# plugV6-Relay-NC-1.net
KiCad netlist of a schematic drawn in EAGLE
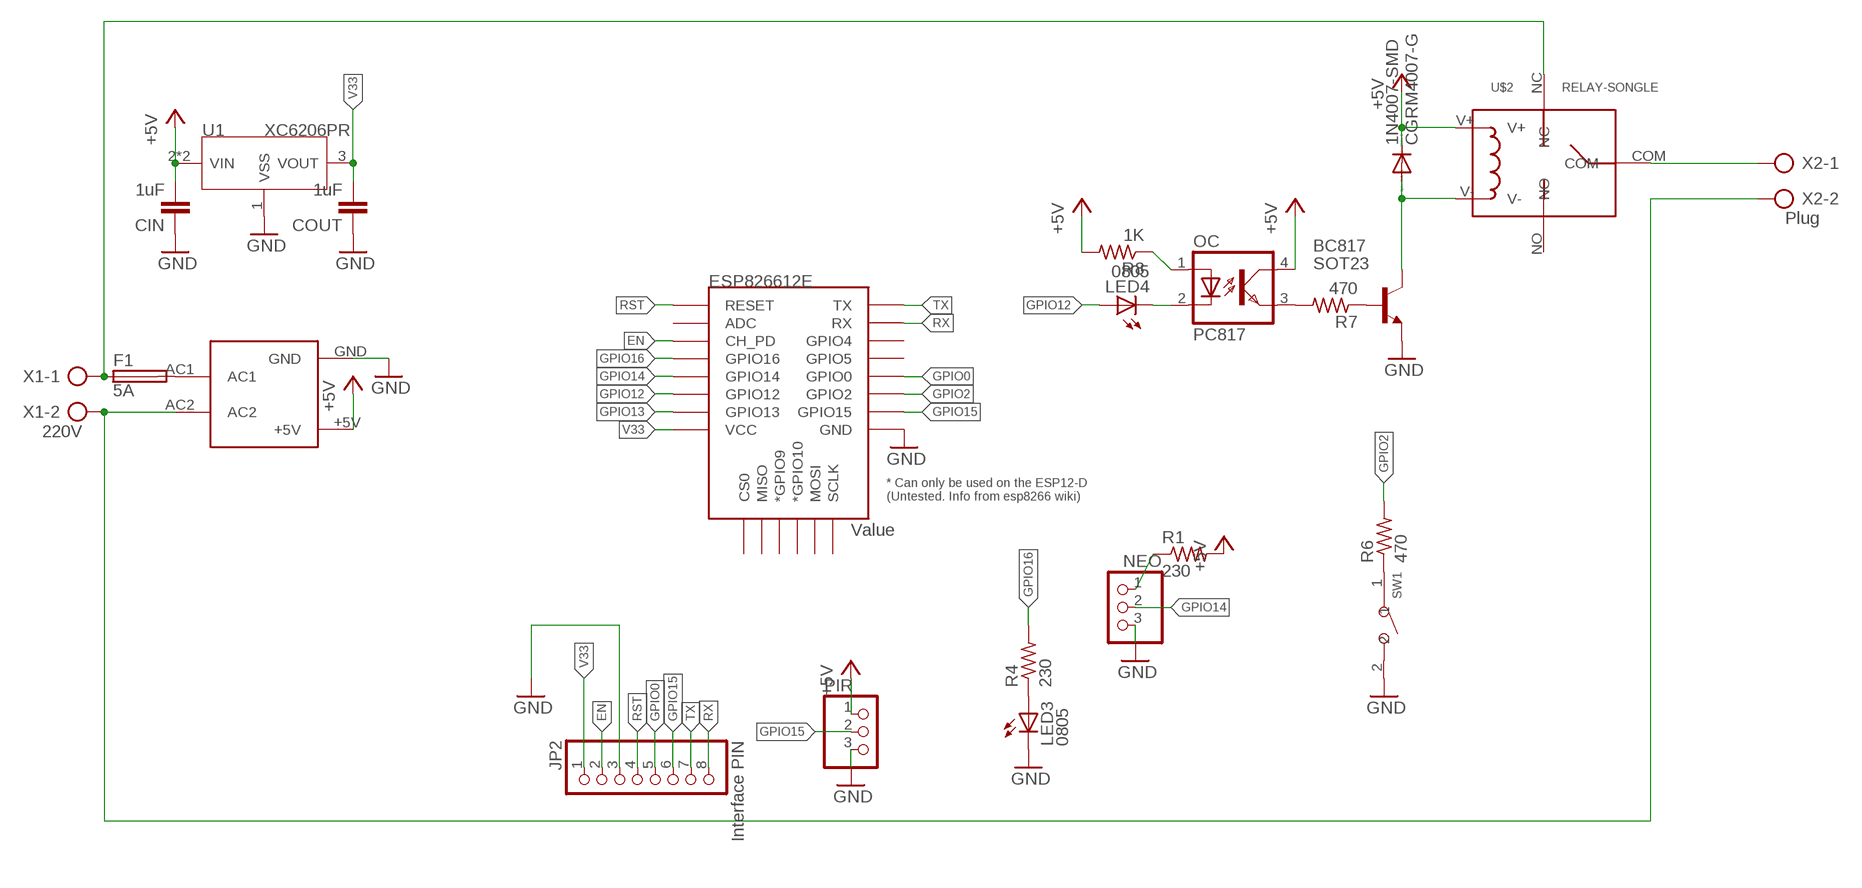
[diagram p0: schematic, sheet 1]

(export (version "E")
  (design (tool "Eeschema 10.0.6"))
  (components
    (comp (ref "1N4007-SMD")
      (value "CGRM4007-G")
      (footprint "eagle-import:SOD-123_MINI-SMA")
      (libsource (lib "eagle-import") (part "CGRM400-G7"))
    )
    (comp (ref "BC817")
      (value "SOT23")
      (footprint "eagle-import:SOT23-BEC")
      (libsource (lib "eagle-import") (part "-NPN-SOT23-BECBC817"))
    )
    (comp (ref "CIN")
      (value "1uF")
      (footprint "eagle-import:C0805")
      (libsource (lib "eagle-import") (part "C-EUC0805"))
    )
    (comp (ref "COUT")
      (value "1uF")
      (footprint "eagle-import:C0805")
      (libsource (lib "eagle-import") (part "C-EUC0805"))
    )
    (comp (ref "ESP826612E")
      (value "Value")
      (footprint "eagle-import:ESP12E-SMD")
      (libsource (lib "eagle-import") (part "ESP12ESMD"))
    )
    (comp (ref "F1")
      (value "5A")
      (footprint "eagle-import:SH22,5A")
      (fields (field (name "MPN") "0031.7701.11"))
      (libsource (lib "eagle-import") (part "SH22,5A"))
    )
    (comp (ref "JP2")
      (value "Interface PIN")
      (footprint "eagle-import:1X08")
      (libsource (lib "eagle-import") (part "PINHD-1X8"))
    )
    (comp (ref "LED3")
      (value "0805")
      (footprint "eagle-import:CHIP-LED0603")
      (libsource (lib "eagle-import") (part "LEDCHIP-LED0603"))
    )
    (comp (ref "LED4")
      (value "0805")
      (footprint "eagle-import:CHIP-LED0603")
      (libsource (lib "eagle-import") (part "LEDCHIP-LED0603"))
    )
    (comp (ref "NEO")
      (value "PINHD-1X3")
      (footprint "eagle-import:1X03")
      (libsource (lib "eagle-import") (part "PINHD-1X3"))
    )
    (comp (ref "OC")
      (value "PC817")
      (footprint "eagle-import:DIL04")
      (fields (field (name "MPN") "PC817X4J000F"))
      (libsource (lib "eagle-import") (part "PC817"))
    )
    (comp (ref "PIR")
      (value "PINHD-1X3")
      (footprint "eagle-import:1X03")
      (libsource (lib "eagle-import") (part "PINHD-1X3"))
    )
    (comp (ref "R1")
      (value "230")
      (footprint "eagle-import:R1206")
      (libsource (lib "eagle-import") (part "R-US_R1206"))
    )
    (comp (ref "R4")
      (value "230")
      (footprint "eagle-import:R1206")
      (libsource (lib "eagle-import") (part "R-US_R1206"))
    )
    (comp (ref "R6")
      (value "470")
      (footprint "eagle-import:R1206")
      (libsource (lib "eagle-import") (part "R-US_R1206"))
    )
    (comp (ref "R7")
      (value "470")
      (footprint "eagle-import:R1206")
      (libsource (lib "eagle-import") (part "R-US_R1206"))
    )
    (comp (ref "R8")
      (value "1K")
      (footprint "eagle-import:R1206")
      (libsource (lib "eagle-import") (part "R-US_R1206"))
    )
    (comp (ref "SW1")
      (value "DIP-BUTTON(2P-6.0X3.0X4.3MM)-TS-1101F")
      (footprint "eagle-import:SW2-5.0-6.0X3.0X4.3MM")
      (libsource (lib "eagle-import") (part "DIP-BUTTON(2P-6.0X3.0X4.3MM)-TS-1101F"))
    )
    (comp (ref "U$1")
      (value "HLK-PM01")
      (footprint "eagle-import:HLK-PM01")
      (libsource (lib "eagle-import") (part "HLK-PM01"))
    )
    (comp (ref "U$2")
      (value "RELAY-SONGLE")
      (footprint "eagle-import:RELAY-SONGLE")
      (libsource (lib "eagle-import") (part "RELAY-SONGLE"))
    )
    (comp (ref "U1")
      (value "XC6206PR")
      (footprint "eagle-import:SOT89")
      (libsource (lib "eagle-import") (part "XC6206PR"))
    )
    (comp (ref "X1")
      (value "220V")
      (footprint "eagle-import:AK300_2")
      (libsource (lib "eagle-import") (part "AK300/2"))
    )
    (comp (ref "X2")
      (value "Plug")
      (footprint "eagle-import:AK300_2")
      (libsource (lib "eagle-import") (part "AK300/2"))
    )
  )
  (nets
    (net (code "1") (name "+5V") (class "Default")
      (node (ref "1N4007-SMD") (pin "C") (pinfunction "C_C") (pintype "passive"))
      (node (ref "CIN") (pin "2") (pinfunction "2_2") (pintype "passive"))
      (node (ref "OC") (pin "4") (pinfunction "COL_4") (pintype "passive"))
      (node (ref "PIR") (pin "1") (pinfunction "1_1") (pintype "passive"))
      (node (ref "R1") (pin "2") (pinfunction "2_2") (pintype "passive"))
      (node (ref "R8") (pin "2") (pinfunction "2_2") (pintype "passive"))
      (node (ref "U$1") (pin "+5V") (pinfunction "+5V_+5V") (pintype "bidirectional"))
      (node (ref "U$2") (pin "V+") (pinfunction "V+_V+") (pintype "bidirectional"))
      (node (ref "U1") (pin "2") (pinfunction "VIN_2") (pintype "input"))
      (node (ref "U1") (pin "4") (pinfunction "VIN_4") (pintype "input"))
    )
    (net (code "2") (name "EN") (class "Default")
      (node (ref "ESP826612E") (pin "CH_PD") (pinfunction "CH_PD_CH_PD") (pintype "bidirectional"))
      (node (ref "JP2") (pin "2") (pinfunction "2_2") (pintype "passive"))
    )
    (net (code "3") (name "GND") (class "Default")
      (node (ref "BC817") (pin "E") (pinfunction "E_E") (pintype "passive"))
      (node (ref "CIN") (pin "1") (pinfunction "1_1") (pintype "passive"))
      (node (ref "COUT") (pin "1") (pinfunction "1_1") (pintype "passive"))
      (node (ref "ESP826612E") (pin "GND") (pinfunction "GND_GND") (pintype "bidirectional"))
      (node (ref "JP2") (pin "3") (pinfunction "3_3") (pintype "passive"))
      (node (ref "LED3") (pin "C") (pinfunction "C_C") (pintype "passive"))
      (node (ref "NEO") (pin "3") (pinfunction "3_3") (pintype "passive"))
      (node (ref "PIR") (pin "3") (pinfunction "3_3") (pintype "passive"))
      (node (ref "SW1") (pin "2") (pinfunction "2_2") (pintype "bidirectional"))
      (node (ref "U$1") (pin "GND") (pinfunction "GND_GND") (pintype "bidirectional"))
      (node (ref "U1") (pin "1") (pinfunction "VSS_1") (pintype "power_in"))
    )
    (net (code "4") (name "GPIO0") (class "Default")
      (node (ref "ESP826612E") (pin "GPIO0") (pinfunction "GPIO0_GPIO0") (pintype "bidirectional"))
      (node (ref "JP2") (pin "5") (pinfunction "5_5") (pintype "passive"))
    )
    (net (code "5") (name "GPIO2") (class "Default")
      (node (ref "ESP826612E") (pin "GPIO2") (pinfunction "GPIO2_GPIO2") (pintype "bidirectional"))
      (node (ref "R6") (pin "2") (pinfunction "2_2") (pintype "passive"))
    )
    (net (code "6") (name "GPIO12") (class "Default")
      (node (ref "ESP826612E") (pin "GPIO12") (pinfunction "GPIO12_GPIO12") (pintype "bidirectional"))
      (node (ref "LED4") (pin "A") (pinfunction "A_A") (pintype "passive"))
    )
    (net (code "7") (name "GPIO13") (class "Default")
      (node (ref "ESP826612E") (pin "GPIO13") (pinfunction "GPIO13_GPIO13") (pintype "bidirectional"))
    )
    (net (code "8") (name "GPIO14") (class "Default")
      (node (ref "ESP826612E") (pin "GPIO14") (pinfunction "GPIO14_GPIO14") (pintype "bidirectional"))
      (node (ref "NEO") (pin "2") (pinfunction "2_2") (pintype "passive"))
    )
    (net (code "9") (name "GPIO15") (class "Default")
      (node (ref "ESP826612E") (pin "GPIO15") (pinfunction "GPIO15_GPIO15") (pintype "bidirectional"))
      (node (ref "JP2") (pin "6") (pinfunction "6_6") (pintype "passive"))
      (node (ref "PIR") (pin "2") (pinfunction "2_2") (pintype "passive"))
    )
    (net (code "10") (name "GPIO16") (class "Default")
      (node (ref "ESP826612E") (pin "GPIO16") (pinfunction "GPIO16_GPIO16") (pintype "bidirectional"))
      (node (ref "R4") (pin "2") (pinfunction "2_2") (pintype "passive"))
    )
    (net (code "11") (name "Net-(1N4007-SMD-PadA)") (class "Default")
      (node (ref "1N4007-SMD") (pin "A") (pinfunction "A_A") (pintype "passive"))
      (node (ref "BC817") (pin "C") (pinfunction "C_C") (pintype "passive"))
      (node (ref "U$2") (pin "V-") (pinfunction "V-_V-") (pintype "bidirectional"))
    )
    (net (code "12") (name "Net-(BC817-PadB)") (class "Default")
      (node (ref "BC817") (pin "B") (pinfunction "B_B") (pintype "passive"))
      (node (ref "R7") (pin "1") (pinfunction "1_1") (pintype "passive"))
    )
    (net (code "13") (name "Net-(F1-Pad2)") (class "Default")
      (node (ref "F1") (pin "2") (pinfunction "2_2") (pintype "passive"))
      (node (ref "U$1") (pin "AC1") (pinfunction "AC1_AC1") (pintype "bidirectional"))
    )
    (net (code "14") (name "Net-(LED3-PadA)") (class "Default")
      (node (ref "LED3") (pin "A") (pinfunction "A_A") (pintype "passive"))
      (node (ref "R4") (pin "1") (pinfunction "1_1") (pintype "passive"))
    )
    (net (code "15") (name "Net-(NEO-Pad1)") (class "Default")
      (node (ref "NEO") (pin "1") (pinfunction "1_1") (pintype "passive"))
      (node (ref "R1") (pin "1") (pinfunction "1_1") (pintype "passive"))
    )
    (net (code "16") (name "Net-(OC-A)") (class "Default")
      (node (ref "OC") (pin "1") (pinfunction "A_1") (pintype "passive"))
      (node (ref "R8") (pin "1") (pinfunction "1_1") (pintype "passive"))
    )
    (net (code "17") (name "Net-(OC-C)") (class "Default")
      (node (ref "LED4") (pin "C") (pinfunction "C_C") (pintype "passive"))
      (node (ref "OC") (pin "2") (pinfunction "C_2") (pintype "passive"))
    )
    (net (code "18") (name "Net-(OC-EMIT)") (class "Default")
      (node (ref "OC") (pin "3") (pinfunction "EMIT_3") (pintype "passive"))
      (node (ref "R7") (pin "2") (pinfunction "2_2") (pintype "passive"))
    )
    (net (code "19") (name "Net-(R6-Pad1)") (class "Default")
      (node (ref "R6") (pin "1") (pinfunction "1_1") (pintype "passive"))
      (node (ref "SW1") (pin "1") (pinfunction "1_1") (pintype "bidirectional"))
    )
    (net (code "20") (name "Net-(X1A-KL)") (class "Default")
      (node (ref "F1") (pin "1") (pinfunction "1_1") (pintype "passive"))
      (node (ref "U$2") (pin "NC") (pinfunction "NC_NC") (pintype "bidirectional"))
      (node (ref "X1") (pin "1") (pinfunction "KL_1") (pintype "passive"))
    )
    (net (code "21") (name "Net-(X1B-KL)") (class "Default")
      (node (ref "U$1") (pin "AC2") (pinfunction "AC2_AC2") (pintype "bidirectional"))
      (node (ref "X1") (pin "2") (pinfunction "KL_2") (pintype "passive"))
      (node (ref "X2") (pin "2") (pinfunction "KL_2") (pintype "passive"))
    )
    (net (code "22") (name "Net-(X2A-KL)") (class "Default")
      (node (ref "U$2") (pin "COM") (pinfunction "COM_COM") (pintype "bidirectional"))
      (node (ref "X2") (pin "1") (pinfunction "KL_1") (pintype "passive"))
    )
    (net (code "23") (name "RST") (class "Default")
      (node (ref "ESP826612E") (pin "RESET") (pinfunction "RESET_RESET") (pintype "bidirectional"))
      (node (ref "JP2") (pin "4") (pinfunction "4_4") (pintype "passive"))
    )
    (net (code "24") (name "RX") (class "Default")
      (node (ref "ESP826612E") (pin "RXD0") (pinfunction "RX_RXD0") (pintype "bidirectional"))
      (node (ref "JP2") (pin "8") (pinfunction "8_8") (pintype "passive"))
    )
    (net (code "25") (name "TX") (class "Default")
      (node (ref "ESP826612E") (pin "TXD0") (pinfunction "TX_TXD0") (pintype "bidirectional"))
      (node (ref "JP2") (pin "7") (pinfunction "7_7") (pintype "passive"))
    )
    (net (code "26") (name "V33") (class "Default")
      (node (ref "COUT") (pin "2") (pinfunction "2_2") (pintype "passive"))
      (node (ref "ESP826612E") (pin "VCC") (pinfunction "VCC_VCC") (pintype "bidirectional"))
      (node (ref "JP2") (pin "1") (pinfunction "1_1") (pintype "passive"))
      (node (ref "U1") (pin "3") (pinfunction "VOUT_3") (pintype "output"))
    )
    (net (code "27") (name "unconnected-(ESP826612E-*GPIO9-PadGPIO9)") (class "Default")
      (node (ref "ESP826612E") (pin "GPIO9") (pinfunction "*GPIO9_GPIO9") (pintype "bidirectional"))
    )
    (net (code "28") (name "unconnected-(ESP826612E-*GPIO10-PadGPIO10)") (class "Default")
      (node (ref "ESP826612E") (pin "GPIO10") (pinfunction "*GPIO10_GPIO10") (pintype "bidirectional"))
    )
    (net (code "29") (name "unconnected-(ESP826612E-PadADC)") (class "Default")
      (node (ref "ESP826612E") (pin "ADC") (pinfunction "ADC_ADC") (pintype "bidirectional"))
    )
    (net (code "30") (name "unconnected-(ESP826612E-PadCS0)") (class "Default")
      (node (ref "ESP826612E") (pin "CS0") (pinfunction "CS0_CS0") (pintype "bidirectional"))
    )
    (net (code "31") (name "unconnected-(ESP826612E-PadGPIO4)") (class "Default")
      (node (ref "ESP826612E") (pin "GPIO4") (pinfunction "GPIO4_GPIO4") (pintype "bidirectional"))
    )
    (net (code "32") (name "unconnected-(ESP826612E-PadGPIO5)") (class "Default")
      (node (ref "ESP826612E") (pin "GPIO5") (pinfunction "GPIO5_GPIO5") (pintype "bidirectional"))
    )
    (net (code "33") (name "unconnected-(ESP826612E-PadMISO)") (class "Default")
      (node (ref "ESP826612E") (pin "MISO") (pinfunction "MISO_MISO") (pintype "bidirectional"))
    )
    (net (code "34") (name "unconnected-(ESP826612E-PadMOSI)") (class "Default")
      (node (ref "ESP826612E") (pin "MOSI") (pinfunction "MOSI_MOSI") (pintype "bidirectional"))
    )
    (net (code "35") (name "unconnected-(ESP826612E-PadSCLK)") (class "Default")
      (node (ref "ESP826612E") (pin "SCLK") (pinfunction "SCLK_SCLK") (pintype "bidirectional"))
    )
    (net (code "36") (name "unconnected-(U$2-PadNO)") (class "Default")
      (node (ref "U$2") (pin "NO") (pinfunction "NO_NO") (pintype "bidirectional"))
    )
  )
)
